# 005_Charger.net
KiCad netlist of a schematic drawn in Altium Designer
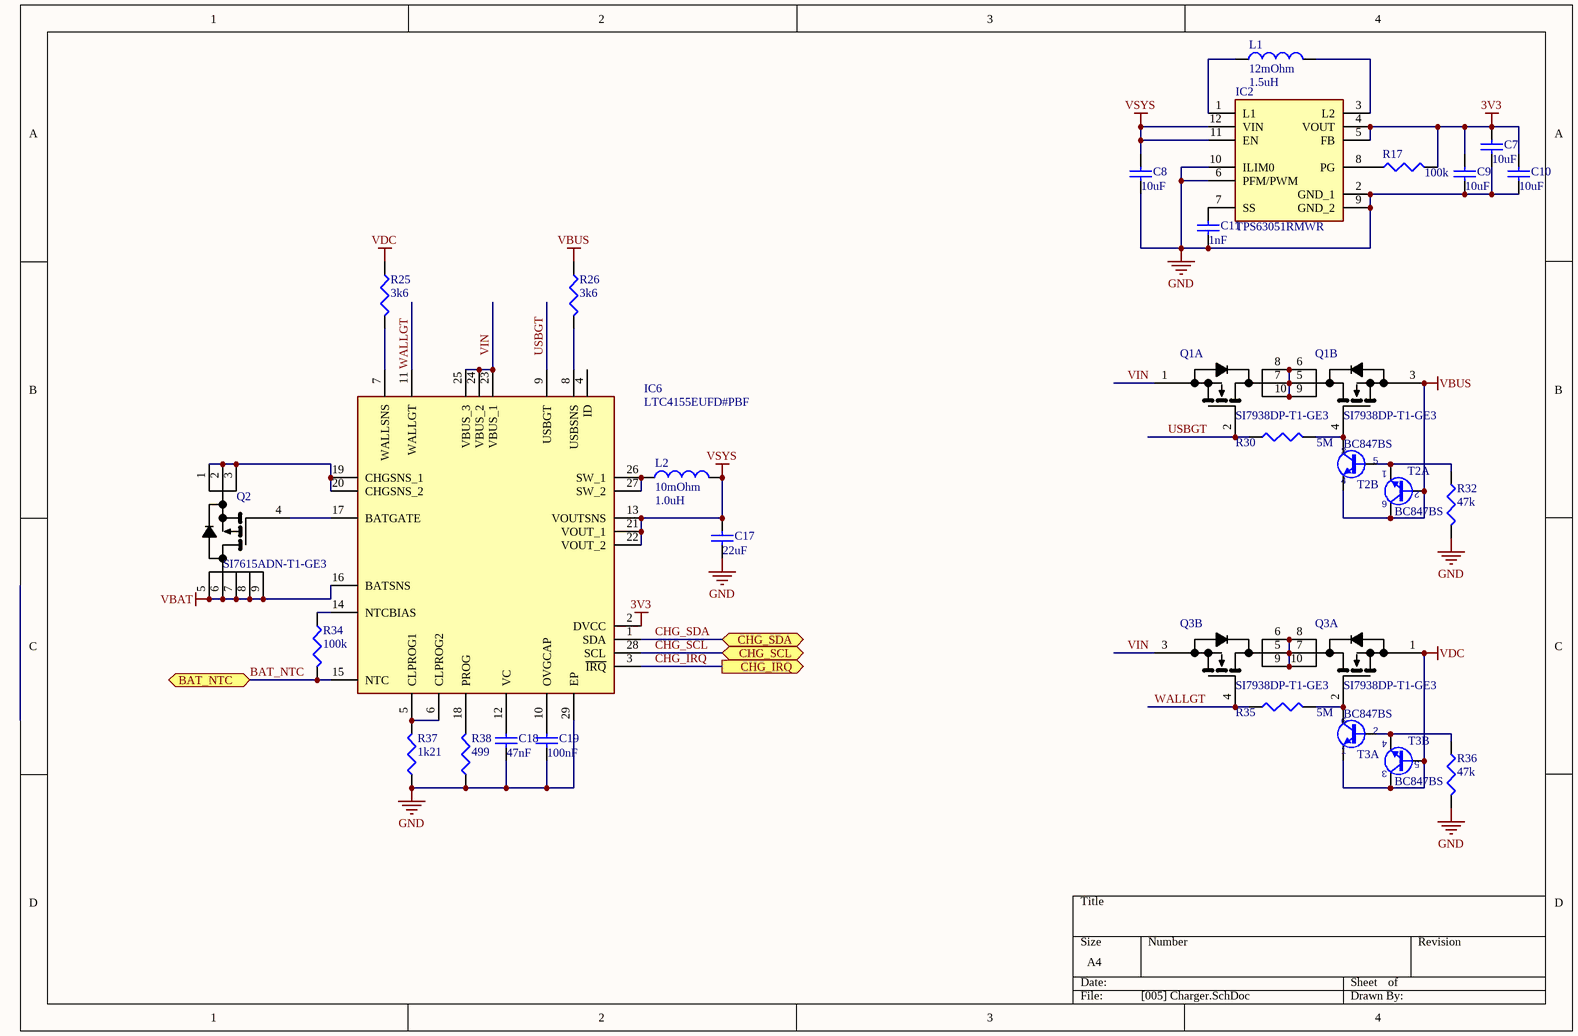
[diagram p0: [005] Charger.SchDoc]

(export (version "E")
  (design (tool "Eeschema 10.0.6"))
  (components
    (comp (ref "C7")
      (value "10uF")
      (footprint "1608[0603]")
      (description "Capacitor (Semiconductor SIM Model)")
      (fields (field (name "Comment") "Cap Semi") (field (name "PUBLISHER") "Altium Limited"))
      (libsource (lib "Miscellaneous Devices") (part "Cap Semi"))
    )
    (comp (ref "C8")
      (value "10uF")
      (footprint "1608[0603]")
      (description "Capacitor (Semiconductor SIM Model)")
      (fields (field (name "Comment") "Cap Semi") (field (name "PUBLISHER") "Altium Limited"))
      (libsource (lib "Miscellaneous Devices") (part "Cap Semi"))
    )
    (comp (ref "C9")
      (value "10uF")
      (footprint "1608[0603]")
      (description "Capacitor (Semiconductor SIM Model)")
      (fields (field (name "Comment") "Cap Semi") (field (name "PUBLISHER") "Altium Limited"))
      (libsource (lib "Miscellaneous Devices") (part "Cap Semi"))
    )
    (comp (ref "C10")
      (value "10uF")
      (footprint "1608[0603]")
      (description "Capacitor (Semiconductor SIM Model)")
      (fields (field (name "Comment") "Cap Semi") (field (name "PUBLISHER") "Altium Limited"))
      (libsource (lib "Miscellaneous Devices") (part "Cap Semi"))
    )
    (comp (ref "C11")
      (value "1nF")
      (footprint "1608[0603]")
      (description "Capacitor (Semiconductor SIM Model)")
      (fields (field (name "Comment") "Cap Semi") (field (name "PUBLISHER") "Altium Limited"))
      (libsource (lib "Miscellaneous Devices") (part "Cap Semi"))
    )
    (comp (ref "C17")
      (value "22uF")
      (footprint "1608[0603]")
      (description "Capacitor (Semiconductor SIM Model)")
      (fields (field (name "Comment") "Cap Semi") (field (name "PUBLISHER") "Altium Limited"))
      (libsource (lib "Miscellaneous Devices") (part "Cap Semi"))
    )
    (comp (ref "C18")
      (value "47nF")
      (footprint "1608[0603]")
      (description "Capacitor (Semiconductor SIM Model)")
      (fields (field (name "Comment") "Cap Semi") (field (name "PUBLISHER") "Altium Limited"))
      (libsource (lib "Miscellaneous Devices") (part "Cap Semi"))
    )
    (comp (ref "C19")
      (value "100nF")
      (footprint "1608[0603]")
      (description "Capacitor (Semiconductor SIM Model)")
      (fields (field (name "Comment") "Cap Semi") (field (name "PUBLISHER") "Altium Limited"))
      (libsource (lib "Miscellaneous Devices") (part "Cap Semi"))
    )
    (comp (ref "IC2")
      (value "TPS63051RMWR")
      (footprint "SamacSys:QFN50P250X250X100-12N-D")
      (description "Integrated Circuit")
      (libsource (lib "SamacSys") (part "TPS63051RMWR"))
    )
    (comp (ref "IC6")
      (value "LTC4155EUFD#PBF")
      (footprint "SamacSys:QFN50P400X500X80-29N-D")
      (description "Integrated Circuit")
      (libsource (lib "SamacSys") (part "LTC4155EUFD#PBF"))
    )
    (comp (ref "L1")
      (value "12mOhm")
      (footprint "INDP2523X23N")
      (description "Inductor SRN6045TA-1R5Y")
      (fields (field (name "ALTIUM_VALUE") "1.5uH") (field (name "PUBLISHER") "Altium Limited"))
      (libsource (lib "Miscellaneous Devices") (part "Inductor"))
    )
    (comp (ref "L2")
      (value "10mOhm")
      (footprint "INDP2523X23N")
      (description "Inductor SRN6045TA-1R0Y")
      (fields (field (name "ALTIUM_VALUE") "1.0uH") (field (name "PUBLISHER") "Altium Limited"))
      (libsource (lib "Miscellaneous Devices") (part "Inductor"))
    )
    (comp (ref "Q1")
      (value "SI7938DP-T1-GE3")
      (footprint "SamacSys:POWERPAK-SO8_1")
      (description "MOSFET (N-Channel)")
      (libsource (lib "SamacSys") (part "SI7938DP-T1-GE3"))
    )
    (comp (ref "Q2")
      (value "SI7615ADN-T1-GE3")
      (footprint "SamacSys:PowerPAK1212-8 Single")
      (description "MOSFET (P-Channel)")
      (fields (field (name "MANUFACTURER_PART_NUMBER") "SIS413DN-T1-GE3"))
      (libsource (lib "SamacSys") (part "SI7615ADN-T1-GE3"))
    )
    (comp (ref "Q3")
      (value "SI7938DP-T1-GE3")
      (footprint "SamacSys:POWERPAK-SO8_1")
      (description "MOSFET (N-Channel)")
      (libsource (lib "SamacSys") (part "SI7938DP-T1-GE3"))
    )
    (comp (ref "R17")
      (value "100k")
      (footprint "J1-0603")
      (description "Resistor")
      (fields (field (name "Comment") "Res3") (field (name "PUBLISHER") "Altium Limited"))
      (libsource (lib "Miscellaneous Devices") (part "Res3"))
    )
    (comp (ref "R25")
      (value "3k6")
      (footprint "J1-0603")
      (description "Resistor")
      (fields (field (name "Comment") "Res3") (field (name "PUBLISHER") "Altium Limited"))
      (libsource (lib "Miscellaneous Devices") (part "Res3"))
    )
    (comp (ref "R26")
      (value "3k6")
      (footprint "J1-0603")
      (description "Resistor")
      (fields (field (name "Comment") "Res3") (field (name "PUBLISHER") "Altium Limited"))
      (libsource (lib "Miscellaneous Devices") (part "Res3"))
    )
    (comp (ref "R30")
      (value "5M")
      (footprint "J1-0603")
      (description "Resistor")
      (fields (field (name "Comment") "Res3") (field (name "PUBLISHER") "Altium Limited"))
      (libsource (lib "Miscellaneous Devices") (part "Res3"))
    )
    (comp (ref "R32")
      (value "47k")
      (footprint "J1-0603")
      (description "Resistor")
      (fields (field (name "Comment") "Res3") (field (name "PUBLISHER") "Altium Limited"))
      (libsource (lib "Miscellaneous Devices") (part "Res3"))
    )
    (comp (ref "R34")
      (value "100k")
      (footprint "J1-0603")
      (description "Resistor")
      (fields (field (name "Comment") "Res3") (field (name "PUBLISHER") "Altium Limited"))
      (libsource (lib "Miscellaneous Devices") (part "Res3"))
    )
    (comp (ref "R35")
      (value "5M")
      (footprint "J1-0603")
      (description "Resistor")
      (fields (field (name "Comment") "Res3") (field (name "PUBLISHER") "Altium Limited"))
      (libsource (lib "Miscellaneous Devices") (part "Res3"))
    )
    (comp (ref "R36")
      (value "47k")
      (footprint "J1-0603")
      (description "Resistor")
      (fields (field (name "Comment") "Res3") (field (name "PUBLISHER") "Altium Limited"))
      (libsource (lib "Miscellaneous Devices") (part "Res3"))
    )
    (comp (ref "R37")
      (value "1k21")
      (footprint "J1-0603")
      (description "Resistor")
      (fields (field (name "Comment") "Res3") (field (name "PUBLISHER") "Altium Limited"))
      (libsource (lib "Miscellaneous Devices") (part "Res3"))
    )
    (comp (ref "R38")
      (value "499")
      (footprint "J1-0603")
      (description "Resistor")
      (fields (field (name "Comment") "Res3") (field (name "PUBLISHER") "Altium Limited"))
      (libsource (lib "Miscellaneous Devices") (part "Res3"))
    )
    (comp (ref "T2")
      (value "BC847BS")
      (footprint "SOT65P210X110-6N")
      (description "45V 100mA Dual NPN General-Purpose Transistor")
      (fields (field (name "MANUFACTURER") "NXP SEMICONDUCTORS") (field (name "AUTHOR") "CERN DEM JMW"))
      (libsource (lib "") (part "BC847BS_1"))
    )
    (comp (ref "T3")
      (value "BC847BS")
      (footprint "SOT65P210X110-6N")
      (description "45V 100mA Dual NPN General-Purpose Transistor")
      (fields (field (name "MANUFACTURER") "NXP SEMICONDUCTORS") (field (name "AUTHOR") "CERN DEM JMW"))
      (libsource (lib "ICs And Semiconductors") (part "BC847BS"))
    )
  )
  (nets
    (net (code "1") (name "/BAT_NTC") (class "Default")
      (node (ref "IC6") (pin "15") (pinfunction "NTC_15") (pintype "passive"))
      (node (ref "R34") (pin "2") (pinfunction "2_2") (pintype "passive"))
    )
    (net (code "2") (name "/CHG_IRQ") (class "Default")
      (node (ref "IC6") (pin "3") (pinfunction "~{IRQ}_3") (pintype "passive"))
    )
    (net (code "3") (name "/CHG_SCL") (class "Default")
      (node (ref "IC6") (pin "28") (pinfunction "SCL_28") (pintype "passive"))
    )
    (net (code "4") (name "/CHG_SDA") (class "Default")
      (node (ref "IC6") (pin "1") (pinfunction "SDA_1") (pintype "passive"))
    )
    (net (code "5") (name "/USBGT") (class "Default")
      (node (ref "IC6") (pin "9") (pinfunction "USBGT_9") (pintype "passive"))
      (node (ref "Q1") (pin "2") (pinfunction "G1_2") (pintype "passive"))
      (node (ref "R30") (pin "1") (pinfunction "1_1") (pintype "passive"))
    )
    (net (code "6") (name "/VIN") (class "Default")
      (node (ref "IC6") (pin "23") (pinfunction "VBUS_1_23") (pintype "passive"))
      (node (ref "IC6") (pin "24") (pinfunction "VBUS_2_24") (pintype "passive"))
      (node (ref "IC6") (pin "25") (pinfunction "VBUS_3_25") (pintype "passive"))
      (node (ref "Q1") (pin "1") (pinfunction "S1_1") (pintype "passive"))
      (node (ref "Q3") (pin "3") (pinfunction "S2_3") (pintype "passive"))
    )
    (net (code "7") (name "/WALLGT") (class "Default")
      (node (ref "IC6") (pin "11") (pinfunction "WALLGT_11") (pintype "passive"))
      (node (ref "Q3") (pin "4") (pinfunction "G2_4") (pintype "passive"))
      (node (ref "R35") (pin "1") (pinfunction "1_1") (pintype "passive"))
    )
    (net (code "8") (name "3V3") (class "Default")
      (node (ref "C10") (pin "2") (pinfunction "2_2") (pintype "passive"))
      (node (ref "C7") (pin "2") (pinfunction "2_2") (pintype "passive"))
      (node (ref "C9") (pin "2") (pinfunction "2_2") (pintype "passive"))
      (node (ref "IC2") (pin "4") (pinfunction "VOUT_4") (pintype "passive"))
      (node (ref "IC2") (pin "5") (pinfunction "FB_5") (pintype "passive"))
      (node (ref "IC6") (pin "2") (pinfunction "DVCC_2") (pintype "passive"))
      (node (ref "R17") (pin "2") (pinfunction "2_2") (pintype "passive"))
    )
    (net (code "9") (name "GND") (class "Default")
      (node (ref "C10") (pin "1") (pinfunction "1_1") (pintype "passive"))
      (node (ref "C11") (pin "1") (pinfunction "1_1") (pintype "passive"))
      (node (ref "C17") (pin "1") (pinfunction "1_1") (pintype "passive"))
      (node (ref "C18") (pin "1") (pinfunction "1_1") (pintype "passive"))
      (node (ref "C19") (pin "1") (pinfunction "1_1") (pintype "passive"))
      (node (ref "C7") (pin "1") (pinfunction "1_1") (pintype "passive"))
      (node (ref "C8") (pin "1") (pinfunction "1_1") (pintype "passive"))
      (node (ref "C9") (pin "1") (pinfunction "1_1") (pintype "passive"))
      (node (ref "IC2") (pin "10") (pinfunction "ILIM0_10") (pintype "passive"))
      (node (ref "IC2") (pin "2") (pinfunction "GND_1_2") (pintype "passive"))
      (node (ref "IC2") (pin "6") (pinfunction "PFM/PWM_6") (pintype "passive"))
      (node (ref "IC2") (pin "9") (pinfunction "GND_2_9") (pintype "passive"))
      (node (ref "IC6") (pin "29") (pinfunction "EP_29") (pintype "passive"))
      (node (ref "R32") (pin "2") (pinfunction "2_2") (pintype "passive"))
      (node (ref "R36") (pin "2") (pinfunction "2_2") (pintype "passive"))
      (node (ref "R37") (pin "1") (pinfunction "1_1") (pintype "passive"))
      (node (ref "R38") (pin "1") (pinfunction "1_1") (pintype "passive"))
    )
    (net (code "10") (name "Net-(IC2-L1)") (class "Default")
      (node (ref "IC2") (pin "1") (pinfunction "L1_1") (pintype "passive"))
      (node (ref "L1") (pin "1") (pinfunction "1_1") (pintype "passive"))
    )
    (net (code "11") (name "Net-(IC2-L2)") (class "Default")
      (node (ref "IC2") (pin "3") (pinfunction "L2_3") (pintype "passive"))
      (node (ref "L1") (pin "2") (pinfunction "2_2") (pintype "passive"))
    )
    (net (code "12") (name "Net-(IC2-PG)") (class "Default")
      (node (ref "IC2") (pin "8") (pinfunction "PG_8") (pintype "passive"))
      (node (ref "R17") (pin "1") (pinfunction "1_1") (pintype "passive"))
    )
    (net (code "13") (name "Net-(IC2-SS)") (class "Default")
      (node (ref "C11") (pin "2") (pinfunction "2_2") (pintype "passive"))
      (node (ref "IC2") (pin "7") (pinfunction "SS_7") (pintype "passive"))
    )
    (net (code "14") (name "Net-(IC6-BATGATE)") (class "Default")
      (node (ref "IC6") (pin "17") (pinfunction "BATGATE_17") (pintype "passive"))
      (node (ref "Q2") (pin "4") (pinfunction "G_4") (pintype "passive"))
    )
    (net (code "15") (name "Net-(IC6-CHGSNS_1)") (class "Default")
      (node (ref "IC6") (pin "19") (pinfunction "CHGSNS_1_19") (pintype "passive"))
      (node (ref "IC6") (pin "20") (pinfunction "CHGSNS_2_20") (pintype "passive"))
      (node (ref "Q2") (pin "1") (pinfunction "S_1") (pintype "passive"))
      (node (ref "Q2") (pin "2") (pinfunction "S_2") (pintype "passive"))
      (node (ref "Q2") (pin "3") (pinfunction "S_3") (pintype "passive"))
    )
    (net (code "16") (name "Net-(IC6-CLPROG1)") (class "Default")
      (node (ref "IC6") (pin "5") (pinfunction "CLPROG1_5") (pintype "passive"))
      (node (ref "IC6") (pin "6") (pinfunction "CLPROG2_6") (pintype "passive"))
      (node (ref "R37") (pin "2") (pinfunction "2_2") (pintype "passive"))
    )
    (net (code "17") (name "Net-(IC6-NTCBIAS)") (class "Default")
      (node (ref "IC6") (pin "14") (pinfunction "NTCBIAS_14") (pintype "passive"))
      (node (ref "R34") (pin "1") (pinfunction "1_1") (pintype "passive"))
    )
    (net (code "18") (name "Net-(IC6-OVGCAP)") (class "Default")
      (node (ref "C19") (pin "2") (pinfunction "2_2") (pintype "passive"))
      (node (ref "IC6") (pin "10") (pinfunction "OVGCAP_10") (pintype "passive"))
    )
    (net (code "19") (name "Net-(IC6-PROG)") (class "Default")
      (node (ref "IC6") (pin "18") (pinfunction "PROG_18") (pintype "passive"))
      (node (ref "R38") (pin "2") (pinfunction "2_2") (pintype "passive"))
    )
    (net (code "20") (name "Net-(IC6-SW_1)") (class "Default")
      (node (ref "IC6") (pin "26") (pinfunction "SW_1_26") (pintype "passive"))
      (node (ref "IC6") (pin "27") (pinfunction "SW_2_27") (pintype "passive"))
      (node (ref "L2") (pin "1") (pinfunction "1_1") (pintype "passive"))
    )
    (net (code "21") (name "Net-(IC6-USBSNS)") (class "Default")
      (node (ref "IC6") (pin "8") (pinfunction "USBSNS_8") (pintype "passive"))
      (node (ref "R26") (pin "2") (pinfunction "2_2") (pintype "passive"))
    )
    (net (code "22") (name "Net-(IC6-VC)") (class "Default")
      (node (ref "C18") (pin "2") (pinfunction "2_2") (pintype "passive"))
      (node (ref "IC6") (pin "12") (pinfunction "VC_12") (pintype "passive"))
    )
    (net (code "23") (name "Net-(IC6-WALLSNS)") (class "Default")
      (node (ref "IC6") (pin "7") (pinfunction "WALLSNS_7") (pintype "passive"))
      (node (ref "R25") (pin "2") (pinfunction "2_2") (pintype "passive"))
    )
    (net (code "24") (name "Net-(Q1A-D1_1)") (class "Default")
      (node (ref "Q1") (pin "10") (pinfunction "D1_3_10") (pintype "passive"))
      (node (ref "Q1") (pin "5") (pinfunction "D2_1_5") (pintype "passive"))
      (node (ref "Q1") (pin "6") (pinfunction "D2_2_6") (pintype "passive"))
      (node (ref "Q1") (pin "7") (pinfunction "D1_1_7") (pintype "passive"))
      (node (ref "Q1") (pin "8") (pinfunction "D1_2_8") (pintype "passive"))
      (node (ref "Q1") (pin "9") (pinfunction "D2_3_9") (pintype "passive"))
    )
    (net (code "25") (name "Net-(Q1B-G2)") (class "Default")
      (node (ref "Q1") (pin "4") (pinfunction "G2_4") (pintype "passive"))
      (node (ref "R30") (pin "2") (pinfunction "2_2") (pintype "passive"))
      (node (ref "T2") (pin "3") (pinfunction "C_3") (pintype "passive"))
    )
    (net (code "26") (name "Net-(Q3A-D1_1)") (class "Default")
      (node (ref "Q3") (pin "10") (pinfunction "D1_3_10") (pintype "passive"))
      (node (ref "Q3") (pin "5") (pinfunction "D2_1_5") (pintype "passive"))
      (node (ref "Q3") (pin "6") (pinfunction "D2_2_6") (pintype "passive"))
      (node (ref "Q3") (pin "7") (pinfunction "D1_1_7") (pintype "passive"))
      (node (ref "Q3") (pin "8") (pinfunction "D1_2_8") (pintype "passive"))
      (node (ref "Q3") (pin "9") (pinfunction "D2_3_9") (pintype "passive"))
    )
    (net (code "27") (name "Net-(Q3A-G1)") (class "Default")
      (node (ref "Q3") (pin "2") (pinfunction "G1_2") (pintype "passive"))
      (node (ref "R35") (pin "2") (pinfunction "2_2") (pintype "passive"))
      (node (ref "T3") (pin "6") (pinfunction "C_6") (pintype "passive"))
    )
    (net (code "28") (name "Net-(T2A-E)") (class "Default")
      (node (ref "R32") (pin "1") (pinfunction "1_1") (pintype "passive"))
      (node (ref "T2") (pin "1") (pinfunction "E_1") (pintype "passive"))
      (node (ref "T2") (pin "5") (pinfunction "B_5") (pintype "passive"))
    )
    (net (code "29") (name "Net-(T3A-B)") (class "Default")
      (node (ref "R36") (pin "1") (pinfunction "1_1") (pintype "passive"))
      (node (ref "T3") (pin "2") (pinfunction "B_2") (pintype "passive"))
      (node (ref "T3") (pin "4") (pinfunction "E_4") (pintype "passive"))
    )
    (net (code "30") (name "VBAT") (class "Default")
      (node (ref "IC6") (pin "16") (pinfunction "BATSNS_16") (pintype "passive"))
      (node (ref "Q2") (pin "5") (pinfunction "D_5") (pintype "passive"))
      (node (ref "Q2") (pin "6") (pinfunction "D_6") (pintype "passive"))
      (node (ref "Q2") (pin "7") (pinfunction "D_7") (pintype "passive"))
      (node (ref "Q2") (pin "8") (pinfunction "D_8") (pintype "passive"))
      (node (ref "Q2") (pin "9") (pinfunction "D_9") (pintype "passive"))
    )
    (net (code "31") (name "VBUS") (class "Default")
      (node (ref "Q1") (pin "3") (pinfunction "S2_3") (pintype "passive"))
      (node (ref "R26") (pin "1") (pinfunction "1_1") (pintype "passive"))
      (node (ref "T2") (pin "2") (pinfunction "B_2") (pintype "passive"))
      (node (ref "T2") (pin "4") (pinfunction "E_4") (pintype "passive"))
      (node (ref "T2") (pin "6") (pinfunction "C_6") (pintype "passive"))
    )
    (net (code "32") (name "VDC") (class "Default")
      (node (ref "Q3") (pin "1") (pinfunction "S1_1") (pintype "passive"))
      (node (ref "R25") (pin "1") (pinfunction "1_1") (pintype "passive"))
      (node (ref "T3") (pin "1") (pinfunction "E_1") (pintype "passive"))
      (node (ref "T3") (pin "3") (pinfunction "C_3") (pintype "passive"))
      (node (ref "T3") (pin "5") (pinfunction "B_5") (pintype "passive"))
    )
    (net (code "33") (name "VSYS") (class "Default")
      (node (ref "C17") (pin "2") (pinfunction "2_2") (pintype "passive"))
      (node (ref "C8") (pin "2") (pinfunction "2_2") (pintype "passive"))
      (node (ref "IC2") (pin "11") (pinfunction "EN_11") (pintype "passive"))
      (node (ref "IC2") (pin "12") (pinfunction "VIN_12") (pintype "passive"))
      (node (ref "IC6") (pin "13") (pinfunction "VOUTSNS_13") (pintype "passive"))
      (node (ref "IC6") (pin "21") (pinfunction "VOUT_1_21") (pintype "passive"))
      (node (ref "IC6") (pin "22") (pinfunction "VOUT_2_22") (pintype "passive"))
      (node (ref "L2") (pin "2") (pinfunction "2_2") (pintype "passive"))
    )
    (net (code "34") (name "unconnected-(IC6-ID-Pad4)") (class "Default")
      (node (ref "IC6") (pin "4") (pinfunction "ID_4") (pintype "passive"))
    )
  )
)
